# 20250811.net
KiCad netlist of a schematic drawn in EasyEDA Pro
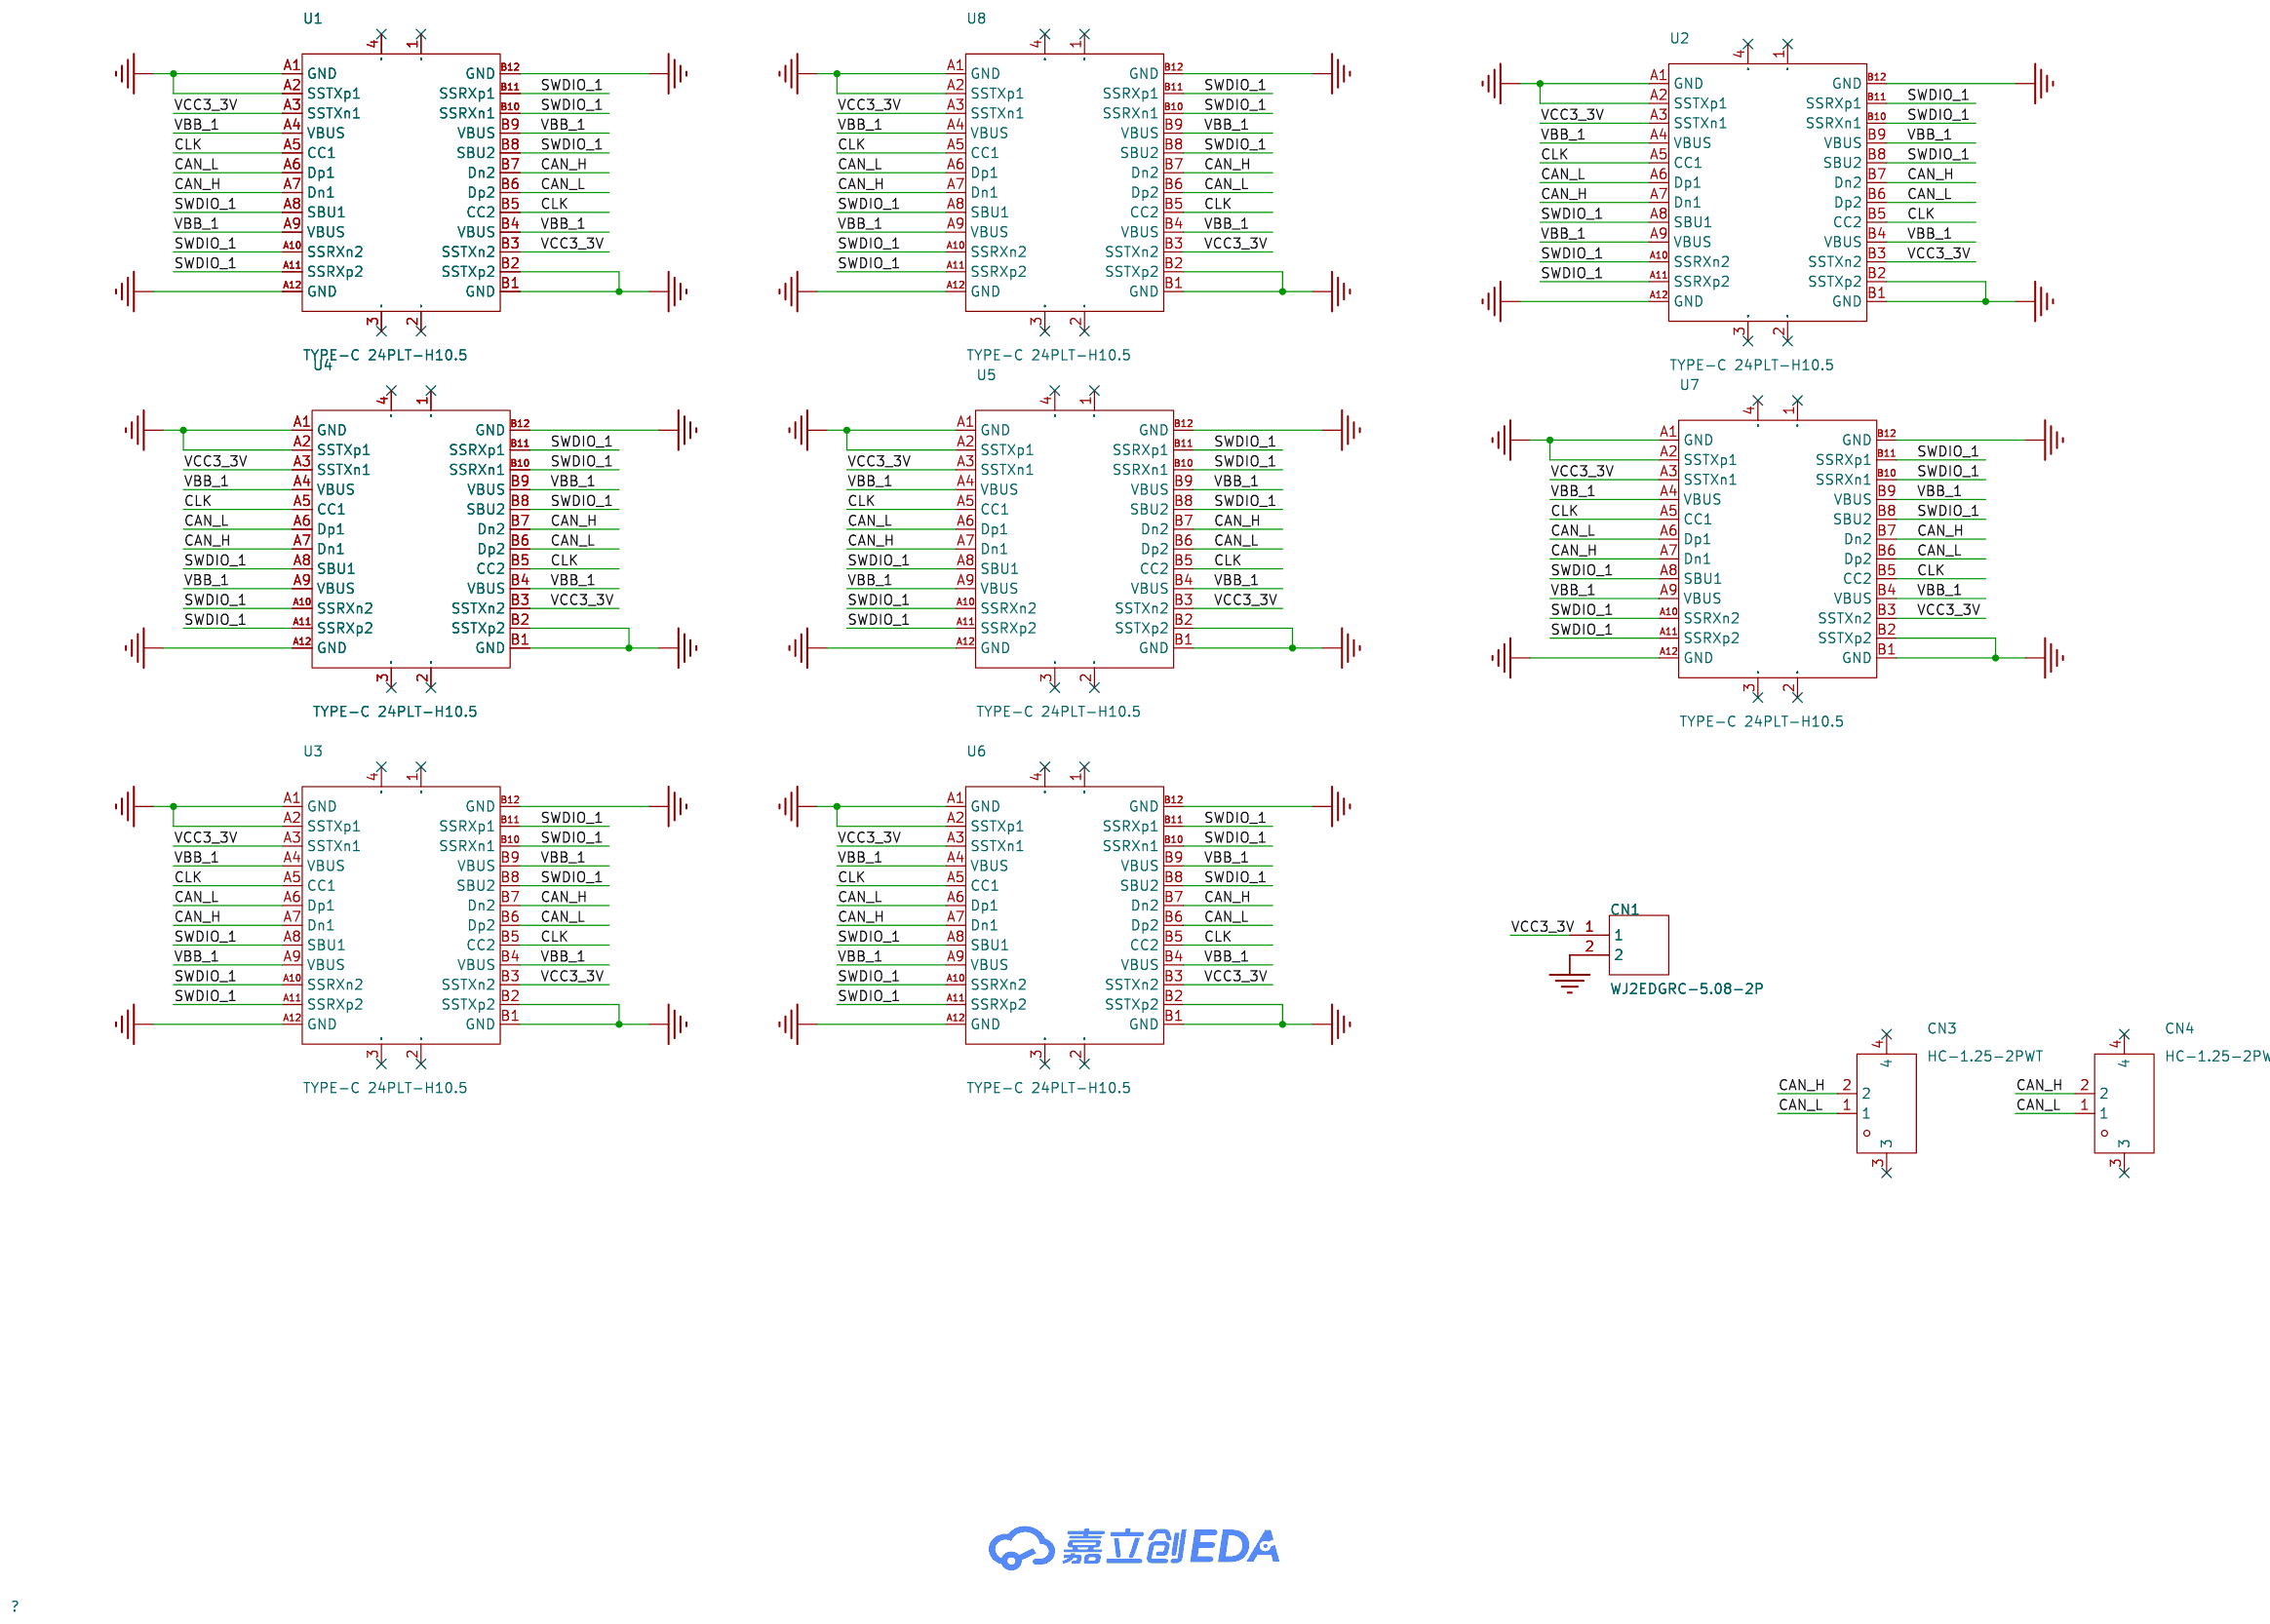
[diagram p0: schematic sheet]

(export (version "E")
  (design (tool "Eeschema 10.0.6"))
  (components
    (comp (ref "CN1")
      (value "WJ2EDGRC-5.08-2P")
      (footprint "easyedapro:CONN-TH_2P-P5.08_WJ2EDGRC-5.08-2P")
      (fields (field (name "Manufacturer") "KANGNEX(康奈克斯电气)"))
      (libsource (lib "easyedapro") (part "WJ2EDGRC-5.08-2P"))
    )
    (comp (ref "CN3")
      (value "HC-1.25-2PWT")
      (footprint "easyedapro:CONN-SMD_2P-P1.25-HC-1.25-2PWT")
      (fields (field (name "Manufacturer") "HCTL(华灿天禄)"))
      (libsource (lib "easyedapro") (part "HC-1.25-2PWT"))
    )
    (comp (ref "CN4")
      (value "HC-1.25-2PWT")
      (footprint "easyedapro:CONN-SMD_2P-P1.25-HC-1.25-2PWT")
      (fields (field (name "Manufacturer") "HCTL(华灿天禄)"))
      (libsource (lib "easyedapro") (part "HC-1.25-2PWT"))
    )
    (comp (ref "U1")
      (value "TYPE-C 24PLT-H10.5")
      (footprint "easyedapro:USB-C_TYPE-C-24PLT-H10.5-1")
      (fields (field (name "Manufacturer") "SHOU HAN(首韩)"))
      (libsource (lib "easyedapro") (part "TYPE-C 24PLT-H10.5"))
    )
    (comp (ref "U2")
      (value "TYPE-C 24PLT-H10.5")
      (footprint "easyedapro:USB-C_TYPE-C-24PLT-H10.5-1")
      (fields (field (name "Manufacturer") "SHOU HAN(首韩)"))
      (libsource (lib "easyedapro") (part "TYPE-C 24PLT-H10.5"))
    )
    (comp (ref "U3")
      (value "TYPE-C 24PLT-H10.5")
      (footprint "easyedapro:USB-C_TYPE-C-24PLT-H10.5-1")
      (fields (field (name "Manufacturer") "SHOU HAN(首韩)"))
      (libsource (lib "easyedapro") (part "TYPE-C 24PLT-H10.5"))
    )
    (comp (ref "U4")
      (value "TYPE-C 24PLT-H10.5")
      (footprint "easyedapro:USB-C_TYPE-C-24PLT-H10.5-1")
      (fields (field (name "Manufacturer") "SHOU HAN(首韩)"))
      (libsource (lib "easyedapro") (part "TYPE-C 24PLT-H10.5"))
    )
    (comp (ref "U5")
      (value "TYPE-C 24PLT-H10.5")
      (footprint "easyedapro:USB-C_TYPE-C-24PLT-H10.5-1")
      (fields (field (name "Manufacturer") "SHOU HAN(首韩)"))
      (libsource (lib "easyedapro") (part "TYPE-C 24PLT-H10.5"))
    )
    (comp (ref "U6")
      (value "TYPE-C 24PLT-H10.5")
      (footprint "easyedapro:USB-C_TYPE-C-24PLT-H10.5-1")
      (fields (field (name "Manufacturer") "SHOU HAN(首韩)"))
      (libsource (lib "easyedapro") (part "TYPE-C 24PLT-H10.5"))
    )
    (comp (ref "U7")
      (value "TYPE-C 24PLT-H10.5")
      (footprint "easyedapro:USB-C_TYPE-C-24PLT-H10.5-1")
      (fields (field (name "Manufacturer") "SHOU HAN(首韩)"))
      (libsource (lib "easyedapro") (part "TYPE-C 24PLT-H10.5"))
    )
    (comp (ref "U8")
      (value "TYPE-C 24PLT-H10.5")
      (footprint "easyedapro:USB-C_TYPE-C-24PLT-H10.5-1")
      (fields (field (name "Manufacturer") "SHOU HAN(首韩)"))
      (libsource (lib "easyedapro") (part "TYPE-C 24PLT-H10.5"))
    )
  )
  (nets
    (net (code "1") (name "/CAN_H") (class "Default")
      (node (ref "CN3") (pin "2") (pinfunction "2_2") (pintype "unspecified"))
      (node (ref "CN4") (pin "2") (pinfunction "2_2") (pintype "unspecified"))
      (node (ref "U1") (pin "A7") (pinfunction "Dn1_A7") (pintype "unspecified"))
      (node (ref "U1") (pin "B7") (pinfunction "Dn2_B7") (pintype "unspecified"))
      (node (ref "U2") (pin "A7") (pinfunction "Dn1_A7") (pintype "unspecified"))
      (node (ref "U2") (pin "B7") (pinfunction "Dn2_B7") (pintype "unspecified"))
      (node (ref "U3") (pin "A7") (pinfunction "Dn1_A7") (pintype "unspecified"))
      (node (ref "U3") (pin "B7") (pinfunction "Dn2_B7") (pintype "unspecified"))
      (node (ref "U4") (pin "A7") (pinfunction "Dn1_A7") (pintype "unspecified"))
      (node (ref "U4") (pin "B7") (pinfunction "Dn2_B7") (pintype "unspecified"))
      (node (ref "U5") (pin "A7") (pinfunction "Dn1_A7") (pintype "unspecified"))
      (node (ref "U5") (pin "B7") (pinfunction "Dn2_B7") (pintype "unspecified"))
      (node (ref "U6") (pin "A7") (pinfunction "Dn1_A7") (pintype "unspecified"))
      (node (ref "U6") (pin "B7") (pinfunction "Dn2_B7") (pintype "unspecified"))
      (node (ref "U7") (pin "A7") (pinfunction "Dn1_A7") (pintype "unspecified"))
      (node (ref "U7") (pin "B7") (pinfunction "Dn2_B7") (pintype "unspecified"))
      (node (ref "U8") (pin "A7") (pinfunction "Dn1_A7") (pintype "unspecified"))
      (node (ref "U8") (pin "B7") (pinfunction "Dn2_B7") (pintype "unspecified"))
    )
    (net (code "2") (name "/CAN_L") (class "Default")
      (node (ref "CN3") (pin "1") (pinfunction "1_1") (pintype "unspecified"))
      (node (ref "CN4") (pin "1") (pinfunction "1_1") (pintype "unspecified"))
      (node (ref "U1") (pin "A6") (pinfunction "Dp1_A6") (pintype "unspecified"))
      (node (ref "U1") (pin "B6") (pinfunction "Dp2_B6") (pintype "unspecified"))
      (node (ref "U2") (pin "A6") (pinfunction "Dp1_A6") (pintype "unspecified"))
      (node (ref "U2") (pin "B6") (pinfunction "Dp2_B6") (pintype "unspecified"))
      (node (ref "U3") (pin "A6") (pinfunction "Dp1_A6") (pintype "unspecified"))
      (node (ref "U3") (pin "B6") (pinfunction "Dp2_B6") (pintype "unspecified"))
      (node (ref "U4") (pin "A6") (pinfunction "Dp1_A6") (pintype "unspecified"))
      (node (ref "U4") (pin "B6") (pinfunction "Dp2_B6") (pintype "unspecified"))
      (node (ref "U5") (pin "A6") (pinfunction "Dp1_A6") (pintype "unspecified"))
      (node (ref "U5") (pin "B6") (pinfunction "Dp2_B6") (pintype "unspecified"))
      (node (ref "U6") (pin "A6") (pinfunction "Dp1_A6") (pintype "unspecified"))
      (node (ref "U6") (pin "B6") (pinfunction "Dp2_B6") (pintype "unspecified"))
      (node (ref "U7") (pin "A6") (pinfunction "Dp1_A6") (pintype "unspecified"))
      (node (ref "U7") (pin "B6") (pinfunction "Dp2_B6") (pintype "unspecified"))
      (node (ref "U8") (pin "A6") (pinfunction "Dp1_A6") (pintype "unspecified"))
      (node (ref "U8") (pin "B6") (pinfunction "Dp2_B6") (pintype "unspecified"))
    )
    (net (code "3") (name "/CLK") (class "Default")
      (node (ref "U1") (pin "A5") (pinfunction "CC1_A5") (pintype "unspecified"))
      (node (ref "U1") (pin "B5") (pinfunction "CC2_B5") (pintype "unspecified"))
      (node (ref "U2") (pin "A5") (pinfunction "CC1_A5") (pintype "unspecified"))
      (node (ref "U2") (pin "B5") (pinfunction "CC2_B5") (pintype "unspecified"))
      (node (ref "U3") (pin "A5") (pinfunction "CC1_A5") (pintype "unspecified"))
      (node (ref "U3") (pin "B5") (pinfunction "CC2_B5") (pintype "unspecified"))
      (node (ref "U4") (pin "A5") (pinfunction "CC1_A5") (pintype "unspecified"))
      (node (ref "U4") (pin "B5") (pinfunction "CC2_B5") (pintype "unspecified"))
      (node (ref "U5") (pin "A5") (pinfunction "CC1_A5") (pintype "unspecified"))
      (node (ref "U5") (pin "B5") (pinfunction "CC2_B5") (pintype "unspecified"))
      (node (ref "U6") (pin "A5") (pinfunction "CC1_A5") (pintype "unspecified"))
      (node (ref "U6") (pin "B5") (pinfunction "CC2_B5") (pintype "unspecified"))
      (node (ref "U7") (pin "A5") (pinfunction "CC1_A5") (pintype "unspecified"))
      (node (ref "U7") (pin "B5") (pinfunction "CC2_B5") (pintype "unspecified"))
      (node (ref "U8") (pin "A5") (pinfunction "CC1_A5") (pintype "unspecified"))
      (node (ref "U8") (pin "B5") (pinfunction "CC2_B5") (pintype "unspecified"))
    )
    (net (code "4") (name "/SWDIO_1") (class "Default")
      (node (ref "U1") (pin "A10") (pinfunction "SSRXn2_A10") (pintype "unspecified"))
      (node (ref "U1") (pin "A11") (pinfunction "SSRXp2_A11") (pintype "unspecified"))
      (node (ref "U1") (pin "A8") (pinfunction "SBU1_A8") (pintype "unspecified"))
      (node (ref "U1") (pin "B10") (pinfunction "SSRXn1_B10") (pintype "unspecified"))
      (node (ref "U1") (pin "B11") (pinfunction "SSRXp1_B11") (pintype "unspecified"))
      (node (ref "U1") (pin "B8") (pinfunction "SBU2_B8") (pintype "unspecified"))
      (node (ref "U2") (pin "A10") (pinfunction "SSRXn2_A10") (pintype "unspecified"))
      (node (ref "U2") (pin "A11") (pinfunction "SSRXp2_A11") (pintype "unspecified"))
      (node (ref "U2") (pin "A8") (pinfunction "SBU1_A8") (pintype "unspecified"))
      (node (ref "U2") (pin "B10") (pinfunction "SSRXn1_B10") (pintype "unspecified"))
      (node (ref "U2") (pin "B11") (pinfunction "SSRXp1_B11") (pintype "unspecified"))
      (node (ref "U2") (pin "B8") (pinfunction "SBU2_B8") (pintype "unspecified"))
      (node (ref "U3") (pin "A10") (pinfunction "SSRXn2_A10") (pintype "unspecified"))
      (node (ref "U3") (pin "A11") (pinfunction "SSRXp2_A11") (pintype "unspecified"))
      (node (ref "U3") (pin "A8") (pinfunction "SBU1_A8") (pintype "unspecified"))
      (node (ref "U3") (pin "B10") (pinfunction "SSRXn1_B10") (pintype "unspecified"))
      (node (ref "U3") (pin "B11") (pinfunction "SSRXp1_B11") (pintype "unspecified"))
      (node (ref "U3") (pin "B8") (pinfunction "SBU2_B8") (pintype "unspecified"))
      (node (ref "U4") (pin "A10") (pinfunction "SSRXn2_A10") (pintype "unspecified"))
      (node (ref "U4") (pin "A11") (pinfunction "SSRXp2_A11") (pintype "unspecified"))
      (node (ref "U4") (pin "A8") (pinfunction "SBU1_A8") (pintype "unspecified"))
      (node (ref "U4") (pin "B10") (pinfunction "SSRXn1_B10") (pintype "unspecified"))
      (node (ref "U4") (pin "B11") (pinfunction "SSRXp1_B11") (pintype "unspecified"))
      (node (ref "U4") (pin "B8") (pinfunction "SBU2_B8") (pintype "unspecified"))
      (node (ref "U5") (pin "A10") (pinfunction "SSRXn2_A10") (pintype "unspecified"))
      (node (ref "U5") (pin "A11") (pinfunction "SSRXp2_A11") (pintype "unspecified"))
      (node (ref "U5") (pin "A8") (pinfunction "SBU1_A8") (pintype "unspecified"))
      (node (ref "U5") (pin "B10") (pinfunction "SSRXn1_B10") (pintype "unspecified"))
      (node (ref "U5") (pin "B11") (pinfunction "SSRXp1_B11") (pintype "unspecified"))
      (node (ref "U5") (pin "B8") (pinfunction "SBU2_B8") (pintype "unspecified"))
      (node (ref "U6") (pin "A10") (pinfunction "SSRXn2_A10") (pintype "unspecified"))
      (node (ref "U6") (pin "A11") (pinfunction "SSRXp2_A11") (pintype "unspecified"))
      (node (ref "U6") (pin "A8") (pinfunction "SBU1_A8") (pintype "unspecified"))
      (node (ref "U6") (pin "B10") (pinfunction "SSRXn1_B10") (pintype "unspecified"))
      (node (ref "U6") (pin "B11") (pinfunction "SSRXp1_B11") (pintype "unspecified"))
      (node (ref "U6") (pin "B8") (pinfunction "SBU2_B8") (pintype "unspecified"))
      (node (ref "U7") (pin "A10") (pinfunction "SSRXn2_A10") (pintype "unspecified"))
      (node (ref "U7") (pin "A11") (pinfunction "SSRXp2_A11") (pintype "unspecified"))
      (node (ref "U7") (pin "A8") (pinfunction "SBU1_A8") (pintype "unspecified"))
      (node (ref "U7") (pin "B10") (pinfunction "SSRXn1_B10") (pintype "unspecified"))
      (node (ref "U7") (pin "B11") (pinfunction "SSRXp1_B11") (pintype "unspecified"))
      (node (ref "U7") (pin "B8") (pinfunction "SBU2_B8") (pintype "unspecified"))
      (node (ref "U8") (pin "A10") (pinfunction "SSRXn2_A10") (pintype "unspecified"))
      (node (ref "U8") (pin "A11") (pinfunction "SSRXp2_A11") (pintype "unspecified"))
      (node (ref "U8") (pin "A8") (pinfunction "SBU1_A8") (pintype "unspecified"))
      (node (ref "U8") (pin "B10") (pinfunction "SSRXn1_B10") (pintype "unspecified"))
      (node (ref "U8") (pin "B11") (pinfunction "SSRXp1_B11") (pintype "unspecified"))
      (node (ref "U8") (pin "B8") (pinfunction "SBU2_B8") (pintype "unspecified"))
    )
    (net (code "5") (name "/VBB_1") (class "Default")
      (node (ref "U1") (pin "A4") (pinfunction "VBUS_A4") (pintype "unspecified"))
      (node (ref "U1") (pin "A9") (pinfunction "VBUS_A9") (pintype "unspecified"))
      (node (ref "U1") (pin "B4") (pinfunction "VBUS_B4") (pintype "unspecified"))
      (node (ref "U1") (pin "B9") (pinfunction "VBUS_B9") (pintype "unspecified"))
      (node (ref "U2") (pin "A4") (pinfunction "VBUS_A4") (pintype "unspecified"))
      (node (ref "U2") (pin "A9") (pinfunction "VBUS_A9") (pintype "unspecified"))
      (node (ref "U2") (pin "B4") (pinfunction "VBUS_B4") (pintype "unspecified"))
      (node (ref "U2") (pin "B9") (pinfunction "VBUS_B9") (pintype "unspecified"))
      (node (ref "U3") (pin "A4") (pinfunction "VBUS_A4") (pintype "unspecified"))
      (node (ref "U3") (pin "A9") (pinfunction "VBUS_A9") (pintype "unspecified"))
      (node (ref "U3") (pin "B4") (pinfunction "VBUS_B4") (pintype "unspecified"))
      (node (ref "U3") (pin "B9") (pinfunction "VBUS_B9") (pintype "unspecified"))
      (node (ref "U4") (pin "A4") (pinfunction "VBUS_A4") (pintype "unspecified"))
      (node (ref "U4") (pin "A9") (pinfunction "VBUS_A9") (pintype "unspecified"))
      (node (ref "U4") (pin "B4") (pinfunction "VBUS_B4") (pintype "unspecified"))
      (node (ref "U4") (pin "B9") (pinfunction "VBUS_B9") (pintype "unspecified"))
      (node (ref "U5") (pin "A4") (pinfunction "VBUS_A4") (pintype "unspecified"))
      (node (ref "U5") (pin "A9") (pinfunction "VBUS_A9") (pintype "unspecified"))
      (node (ref "U5") (pin "B4") (pinfunction "VBUS_B4") (pintype "unspecified"))
      (node (ref "U5") (pin "B9") (pinfunction "VBUS_B9") (pintype "unspecified"))
      (node (ref "U6") (pin "A4") (pinfunction "VBUS_A4") (pintype "unspecified"))
      (node (ref "U6") (pin "A9") (pinfunction "VBUS_A9") (pintype "unspecified"))
      (node (ref "U6") (pin "B4") (pinfunction "VBUS_B4") (pintype "unspecified"))
      (node (ref "U6") (pin "B9") (pinfunction "VBUS_B9") (pintype "unspecified"))
      (node (ref "U7") (pin "A4") (pinfunction "VBUS_A4") (pintype "unspecified"))
      (node (ref "U7") (pin "A9") (pinfunction "VBUS_A9") (pintype "unspecified"))
      (node (ref "U7") (pin "B4") (pinfunction "VBUS_B4") (pintype "unspecified"))
      (node (ref "U7") (pin "B9") (pinfunction "VBUS_B9") (pintype "unspecified"))
      (node (ref "U8") (pin "A4") (pinfunction "VBUS_A4") (pintype "unspecified"))
      (node (ref "U8") (pin "A9") (pinfunction "VBUS_A9") (pintype "unspecified"))
      (node (ref "U8") (pin "B4") (pinfunction "VBUS_B4") (pintype "unspecified"))
      (node (ref "U8") (pin "B9") (pinfunction "VBUS_B9") (pintype "unspecified"))
    )
    (net (code "6") (name "/VCC3_3V") (class "Default")
      (node (ref "CN1") (pin "1") (pinfunction "1_1") (pintype "unspecified"))
      (node (ref "U1") (pin "A3") (pinfunction "SSTXn1_A3") (pintype "unspecified"))
      (node (ref "U1") (pin "B3") (pinfunction "SSTXn2_B3") (pintype "unspecified"))
      (node (ref "U2") (pin "A3") (pinfunction "SSTXn1_A3") (pintype "unspecified"))
      (node (ref "U2") (pin "B3") (pinfunction "SSTXn2_B3") (pintype "unspecified"))
      (node (ref "U3") (pin "A3") (pinfunction "SSTXn1_A3") (pintype "unspecified"))
      (node (ref "U3") (pin "B3") (pinfunction "SSTXn2_B3") (pintype "unspecified"))
      (node (ref "U4") (pin "A3") (pinfunction "SSTXn1_A3") (pintype "unspecified"))
      (node (ref "U4") (pin "B3") (pinfunction "SSTXn2_B3") (pintype "unspecified"))
      (node (ref "U5") (pin "A3") (pinfunction "SSTXn1_A3") (pintype "unspecified"))
      (node (ref "U5") (pin "B3") (pinfunction "SSTXn2_B3") (pintype "unspecified"))
      (node (ref "U6") (pin "A3") (pinfunction "SSTXn1_A3") (pintype "unspecified"))
      (node (ref "U6") (pin "B3") (pinfunction "SSTXn2_B3") (pintype "unspecified"))
      (node (ref "U7") (pin "A3") (pinfunction "SSTXn1_A3") (pintype "unspecified"))
      (node (ref "U7") (pin "B3") (pinfunction "SSTXn2_B3") (pintype "unspecified"))
      (node (ref "U8") (pin "A3") (pinfunction "SSTXn1_A3") (pintype "unspecified"))
      (node (ref "U8") (pin "B3") (pinfunction "SSTXn2_B3") (pintype "unspecified"))
    )
    (net (code "7") (name "GND") (class "Default")
      (node (ref "CN1") (pin "2") (pinfunction "2_2") (pintype "unspecified"))
      (node (ref "U1") (pin "A1") (pinfunction "GND_A1") (pintype "unspecified"))
      (node (ref "U1") (pin "A12") (pinfunction "GND_A12") (pintype "unspecified"))
      (node (ref "U1") (pin "A2") (pinfunction "SSTXp1_A2") (pintype "unspecified"))
      (node (ref "U1") (pin "B1") (pinfunction "GND_B1") (pintype "unspecified"))
      (node (ref "U1") (pin "B12") (pinfunction "GND_B12") (pintype "unspecified"))
      (node (ref "U1") (pin "B2") (pinfunction "SSTXp2_B2") (pintype "unspecified"))
      (node (ref "U2") (pin "A1") (pinfunction "GND_A1") (pintype "unspecified"))
      (node (ref "U2") (pin "A12") (pinfunction "GND_A12") (pintype "unspecified"))
      (node (ref "U2") (pin "A2") (pinfunction "SSTXp1_A2") (pintype "unspecified"))
      (node (ref "U2") (pin "B1") (pinfunction "GND_B1") (pintype "unspecified"))
      (node (ref "U2") (pin "B12") (pinfunction "GND_B12") (pintype "unspecified"))
      (node (ref "U2") (pin "B2") (pinfunction "SSTXp2_B2") (pintype "unspecified"))
      (node (ref "U3") (pin "A1") (pinfunction "GND_A1") (pintype "unspecified"))
      (node (ref "U3") (pin "A12") (pinfunction "GND_A12") (pintype "unspecified"))
      (node (ref "U3") (pin "A2") (pinfunction "SSTXp1_A2") (pintype "unspecified"))
      (node (ref "U3") (pin "B1") (pinfunction "GND_B1") (pintype "unspecified"))
      (node (ref "U3") (pin "B12") (pinfunction "GND_B12") (pintype "unspecified"))
      (node (ref "U3") (pin "B2") (pinfunction "SSTXp2_B2") (pintype "unspecified"))
      (node (ref "U4") (pin "A1") (pinfunction "GND_A1") (pintype "unspecified"))
      (node (ref "U4") (pin "A12") (pinfunction "GND_A12") (pintype "unspecified"))
      (node (ref "U4") (pin "A2") (pinfunction "SSTXp1_A2") (pintype "unspecified"))
      (node (ref "U4") (pin "B1") (pinfunction "GND_B1") (pintype "unspecified"))
      (node (ref "U4") (pin "B12") (pinfunction "GND_B12") (pintype "unspecified"))
      (node (ref "U4") (pin "B2") (pinfunction "SSTXp2_B2") (pintype "unspecified"))
      (node (ref "U5") (pin "A1") (pinfunction "GND_A1") (pintype "unspecified"))
      (node (ref "U5") (pin "A12") (pinfunction "GND_A12") (pintype "unspecified"))
      (node (ref "U5") (pin "A2") (pinfunction "SSTXp1_A2") (pintype "unspecified"))
      (node (ref "U5") (pin "B1") (pinfunction "GND_B1") (pintype "unspecified"))
      (node (ref "U5") (pin "B12") (pinfunction "GND_B12") (pintype "unspecified"))
      (node (ref "U5") (pin "B2") (pinfunction "SSTXp2_B2") (pintype "unspecified"))
      (node (ref "U6") (pin "A1") (pinfunction "GND_A1") (pintype "unspecified"))
      (node (ref "U6") (pin "A12") (pinfunction "GND_A12") (pintype "unspecified"))
      (node (ref "U6") (pin "A2") (pinfunction "SSTXp1_A2") (pintype "unspecified"))
      (node (ref "U6") (pin "B1") (pinfunction "GND_B1") (pintype "unspecified"))
      (node (ref "U6") (pin "B12") (pinfunction "GND_B12") (pintype "unspecified"))
      (node (ref "U6") (pin "B2") (pinfunction "SSTXp2_B2") (pintype "unspecified"))
      (node (ref "U7") (pin "A1") (pinfunction "GND_A1") (pintype "unspecified"))
      (node (ref "U7") (pin "A12") (pinfunction "GND_A12") (pintype "unspecified"))
      (node (ref "U7") (pin "A2") (pinfunction "SSTXp1_A2") (pintype "unspecified"))
      (node (ref "U7") (pin "B1") (pinfunction "GND_B1") (pintype "unspecified"))
      (node (ref "U7") (pin "B12") (pinfunction "GND_B12") (pintype "unspecified"))
      (node (ref "U7") (pin "B2") (pinfunction "SSTXp2_B2") (pintype "unspecified"))
      (node (ref "U8") (pin "A1") (pinfunction "GND_A1") (pintype "unspecified"))
      (node (ref "U8") (pin "A12") (pinfunction "GND_A12") (pintype "unspecified"))
      (node (ref "U8") (pin "A2") (pinfunction "SSTXp1_A2") (pintype "unspecified"))
      (node (ref "U8") (pin "B1") (pinfunction "GND_B1") (pintype "unspecified"))
      (node (ref "U8") (pin "B12") (pinfunction "GND_B12") (pintype "unspecified"))
      (node (ref "U8") (pin "B2") (pinfunction "SSTXp2_B2") (pintype "unspecified"))
    )
    (net (code "8") (name "unconnected-(CN3-Pad3)") (class "Default")
      (node (ref "CN3") (pin "3") (pinfunction "3_3") (pintype "unspecified+no_connect"))
    )
    (net (code "9") (name "unconnected-(CN3-Pad4)") (class "Default")
      (node (ref "CN3") (pin "4") (pinfunction "4_4") (pintype "unspecified+no_connect"))
    )
    (net (code "10") (name "unconnected-(CN4-Pad3)") (class "Default")
      (node (ref "CN4") (pin "3") (pinfunction "3_3") (pintype "unspecified+no_connect"))
    )
    (net (code "11") (name "unconnected-(CN4-Pad4)") (class "Default")
      (node (ref "CN4") (pin "4") (pinfunction "4_4") (pintype "unspecified+no_connect"))
    )
    (net (code "12") (name "unconnected-(U1-SHEELD-Pad1)") (class "Default")
      (node (ref "U1") (pin "1") (pinfunction "SHEELD_1") (pintype "unspecified+no_connect"))
    )
    (net (code "13") (name "unconnected-(U1-SHEELD-Pad2)") (class "Default")
      (node (ref "U1") (pin "2") (pinfunction "SHEELD_2") (pintype "unspecified+no_connect"))
    )
    (net (code "14") (name "unconnected-(U1-SHEELD-Pad3)") (class "Default")
      (node (ref "U1") (pin "3") (pinfunction "SHEELD_3") (pintype "unspecified+no_connect"))
    )
    (net (code "15") (name "unconnected-(U1-SHEELD-Pad4)") (class "Default")
      (node (ref "U1") (pin "4") (pinfunction "SHEELD_4") (pintype "unspecified+no_connect"))
    )
    (net (code "16") (name "unconnected-(U2-SHEELD-Pad1)") (class "Default")
      (node (ref "U2") (pin "1") (pinfunction "SHEELD_1") (pintype "unspecified+no_connect"))
    )
    (net (code "17") (name "unconnected-(U2-SHEELD-Pad2)") (class "Default")
      (node (ref "U2") (pin "2") (pinfunction "SHEELD_2") (pintype "unspecified+no_connect"))
    )
    (net (code "18") (name "unconnected-(U2-SHEELD-Pad3)") (class "Default")
      (node (ref "U2") (pin "3") (pinfunction "SHEELD_3") (pintype "unspecified+no_connect"))
    )
    (net (code "19") (name "unconnected-(U2-SHEELD-Pad4)") (class "Default")
      (node (ref "U2") (pin "4") (pinfunction "SHEELD_4") (pintype "unspecified+no_connect"))
    )
    (net (code "20") (name "unconnected-(U3-SHEELD-Pad1)") (class "Default")
      (node (ref "U3") (pin "1") (pinfunction "SHEELD_1") (pintype "unspecified+no_connect"))
    )
    (net (code "21") (name "unconnected-(U3-SHEELD-Pad2)") (class "Default")
      (node (ref "U3") (pin "2") (pinfunction "SHEELD_2") (pintype "unspecified+no_connect"))
    )
    (net (code "22") (name "unconnected-(U3-SHEELD-Pad3)") (class "Default")
      (node (ref "U3") (pin "3") (pinfunction "SHEELD_3") (pintype "unspecified+no_connect"))
    )
    (net (code "23") (name "unconnected-(U3-SHEELD-Pad4)") (class "Default")
      (node (ref "U3") (pin "4") (pinfunction "SHEELD_4") (pintype "unspecified+no_connect"))
    )
    (net (code "24") (name "unconnected-(U4-SHEELD-Pad1)") (class "Default")
      (node (ref "U4") (pin "1") (pinfunction "SHEELD_1") (pintype "unspecified+no_connect"))
    )
    (net (code "25") (name "unconnected-(U4-SHEELD-Pad2)") (class "Default")
      (node (ref "U4") (pin "2") (pinfunction "SHEELD_2") (pintype "unspecified+no_connect"))
    )
    (net (code "26") (name "unconnected-(U4-SHEELD-Pad3)") (class "Default")
      (node (ref "U4") (pin "3") (pinfunction "SHEELD_3") (pintype "unspecified+no_connect"))
    )
    (net (code "27") (name "unconnected-(U4-SHEELD-Pad4)") (class "Default")
      (node (ref "U4") (pin "4") (pinfunction "SHEELD_4") (pintype "unspecified+no_connect"))
    )
    (net (code "28") (name "unconnected-(U5-SHEELD-Pad1)") (class "Default")
      (node (ref "U5") (pin "1") (pinfunction "SHEELD_1") (pintype "unspecified+no_connect"))
    )
    (net (code "29") (name "unconnected-(U5-SHEELD-Pad2)") (class "Default")
      (node (ref "U5") (pin "2") (pinfunction "SHEELD_2") (pintype "unspecified+no_connect"))
    )
    (net (code "30") (name "unconnected-(U5-SHEELD-Pad3)") (class "Default")
      (node (ref "U5") (pin "3") (pinfunction "SHEELD_3") (pintype "unspecified+no_connect"))
    )
    (net (code "31") (name "unconnected-(U5-SHEELD-Pad4)") (class "Default")
      (node (ref "U5") (pin "4") (pinfunction "SHEELD_4") (pintype "unspecified+no_connect"))
    )
    (net (code "32") (name "unconnected-(U6-SHEELD-Pad1)") (class "Default")
      (node (ref "U6") (pin "1") (pinfunction "SHEELD_1") (pintype "unspecified+no_connect"))
    )
    (net (code "33") (name "unconnected-(U6-SHEELD-Pad2)") (class "Default")
      (node (ref "U6") (pin "2") (pinfunction "SHEELD_2") (pintype "unspecified+no_connect"))
    )
    (net (code "34") (name "unconnected-(U6-SHEELD-Pad3)") (class "Default")
      (node (ref "U6") (pin "3") (pinfunction "SHEELD_3") (pintype "unspecified+no_connect"))
    )
    (net (code "35") (name "unconnected-(U6-SHEELD-Pad4)") (class "Default")
      (node (ref "U6") (pin "4") (pinfunction "SHEELD_4") (pintype "unspecified+no_connect"))
    )
    (net (code "36") (name "unconnected-(U7-SHEELD-Pad1)") (class "Default")
      (node (ref "U7") (pin "1") (pinfunction "SHEELD_1") (pintype "unspecified+no_connect"))
    )
    (net (code "37") (name "unconnected-(U7-SHEELD-Pad2)") (class "Default")
      (node (ref "U7") (pin "2") (pinfunction "SHEELD_2") (pintype "unspecified+no_connect"))
    )
    (net (code "38") (name "unconnected-(U7-SHEELD-Pad3)") (class "Default")
      (node (ref "U7") (pin "3") (pinfunction "SHEELD_3") (pintype "unspecified+no_connect"))
    )
    (net (code "39") (name "unconnected-(U7-SHEELD-Pad4)") (class "Default")
      (node (ref "U7") (pin "4") (pinfunction "SHEELD_4") (pintype "unspecified+no_connect"))
    )
    (net (code "40") (name "unconnected-(U8-SHEELD-Pad1)") (class "Default")
      (node (ref "U8") (pin "1") (pinfunction "SHEELD_1") (pintype "unspecified+no_connect"))
    )
    (net (code "41") (name "unconnected-(U8-SHEELD-Pad2)") (class "Default")
      (node (ref "U8") (pin "2") (pinfunction "SHEELD_2") (pintype "unspecified+no_connect"))
    )
    (net (code "42") (name "unconnected-(U8-SHEELD-Pad3)") (class "Default")
      (node (ref "U8") (pin "3") (pinfunction "SHEELD_3") (pintype "unspecified+no_connect"))
    )
    (net (code "43") (name "unconnected-(U8-SHEELD-Pad4)") (class "Default")
      (node (ref "U8") (pin "4") (pinfunction "SHEELD_4") (pintype "unspecified+no_connect"))
    )
  )
)
